# PingPong_388_2019_rev6.net
KiCad netlist of a schematic drawn in EAGLE
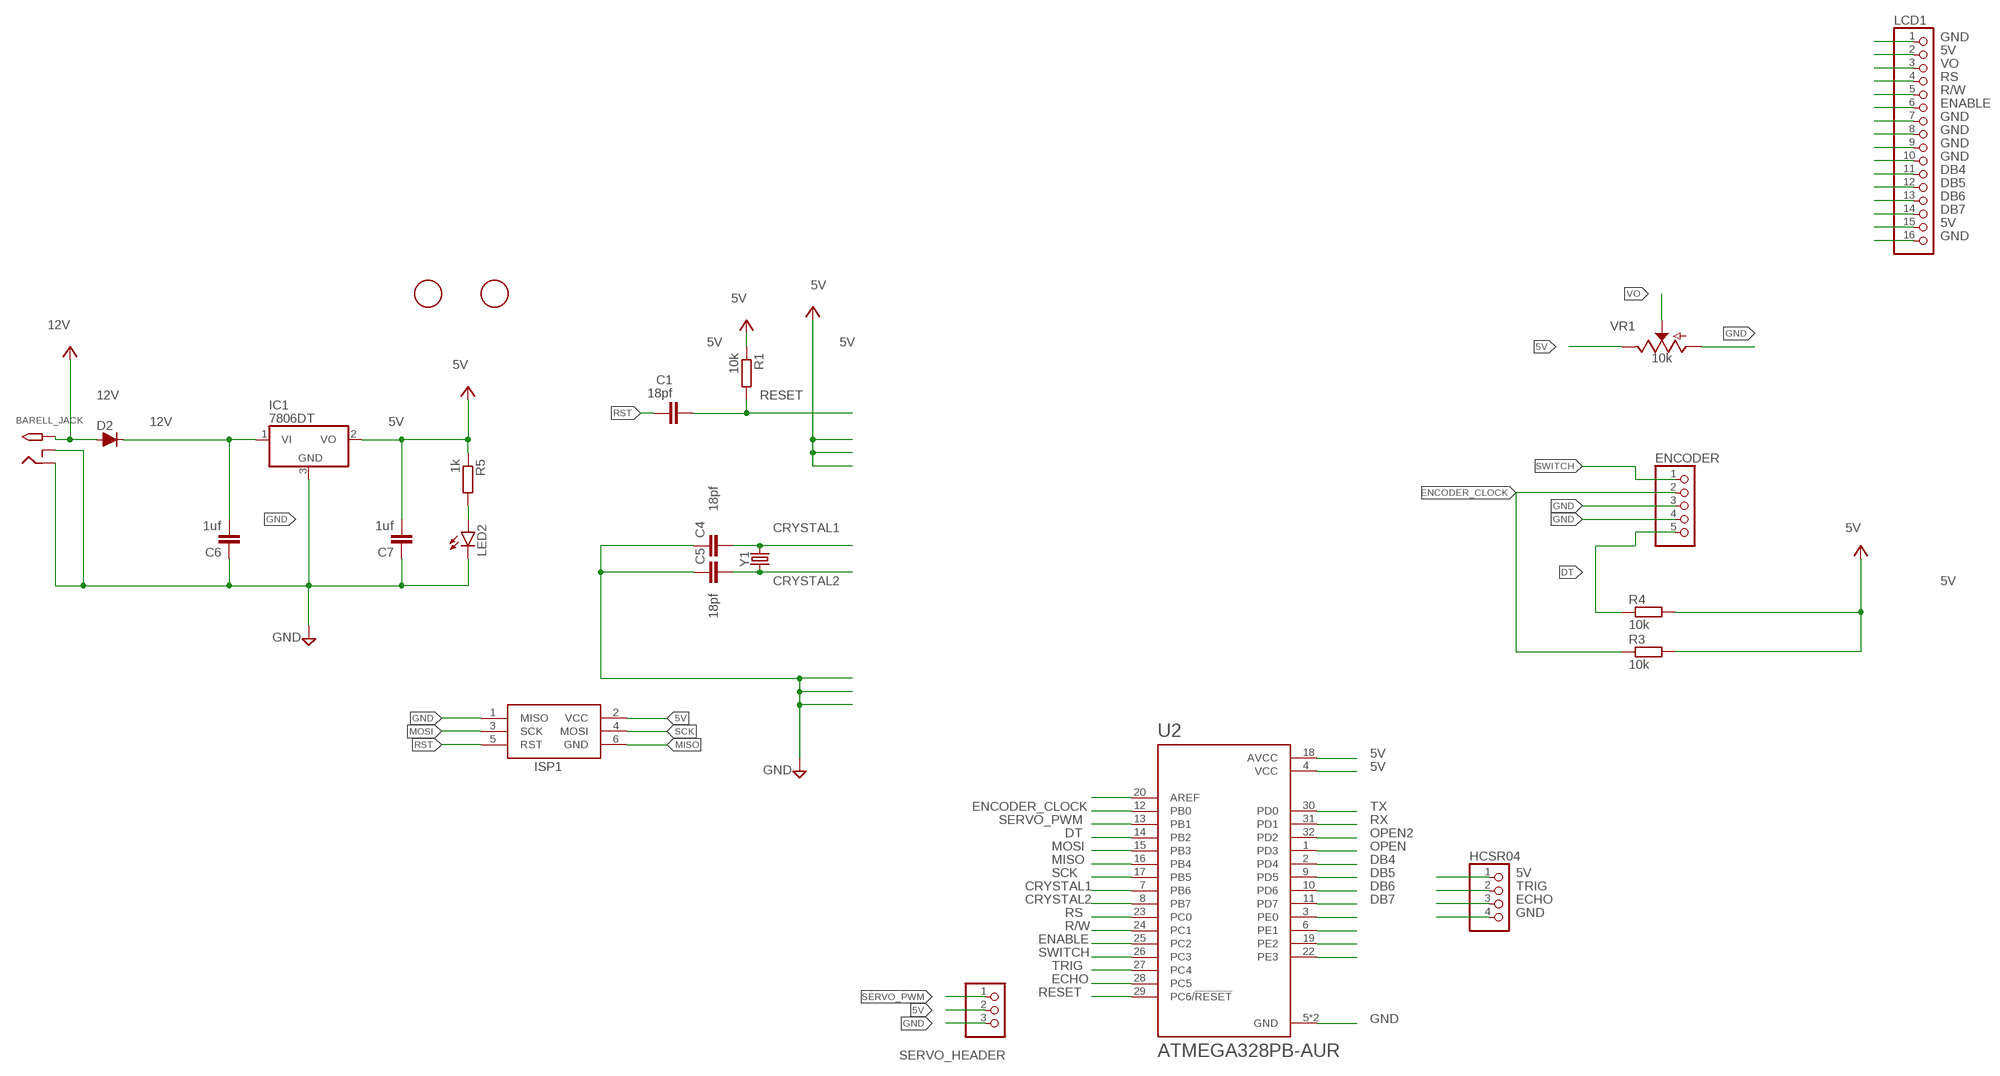
[diagram p0: schematic, sheet 1]

(export (version "E")
  (design (tool "Eeschema 10.0.6"))
  (components
    (comp (ref "BARELL_JACK")
      (value "2.1MMJACKTHM")
      (footprint "eagle-import:PJ-102A")
      (libsource (lib "eagle-import") (part "2.1MMJACKTHM"))
    )
    (comp (ref "C1")
      (value "18pf")
      (footprint "eagle-import:C0805")
      (libsource (lib "eagle-import") (part "C-EUC0805"))
    )
    (comp (ref "C4")
      (value "18pf")
      (footprint "eagle-import:C0805")
      (libsource (lib "eagle-import") (part "C-EUC0805"))
    )
    (comp (ref "C5")
      (value "18pf")
      (footprint "eagle-import:C0805")
      (libsource (lib "eagle-import") (part "C-EUC0805"))
    )
    (comp (ref "C6")
      (value "1uf")
      (footprint "eagle-import:C0805")
      (libsource (lib "eagle-import") (part "C-EUC0805"))
    )
    (comp (ref "C7")
      (value "1uf")
      (footprint "eagle-import:C0805")
      (libsource (lib "eagle-import") (part "C-EUC0805"))
    )
    (comp (ref "D2")
      (value "D-FILL-MLL-34")
      (footprint "eagle-import:MELF-MLL34")
      (libsource (lib "eagle-import") (part "D-FILL-MLL-34"))
    )
    (comp (ref "ENCODER")
      (value "PINHD-1X5")
      (footprint "eagle-import:1X05")
      (libsource (lib "eagle-import") (part "PINHD-1X5"))
    )
    (comp (ref "HCSR04")
      (value "PINHD-1X4")
      (footprint "eagle-import:1X04")
      (libsource (lib "eagle-import") (part "PINHD-1X4"))
    )
    (comp (ref "IC1")
      (value "7806DT")
      (footprint "eagle-import:TO252")
      (libsource (lib "eagle-import") (part "78DT06"))
    )
    (comp (ref "ISP1")
      (value "AVRISP-6")
      (footprint "eagle-import:AVRISP")
      (libsource (lib "eagle-import") (part "AVRISP-6"))
    )
    (comp (ref "LCD1")
      (value "PINHD-1X16")
      (footprint "eagle-import:1X16")
      (libsource (lib "eagle-import") (part "PINHD-1X16"))
    )
    (comp (ref "LED2")
      (value "LEDSML0805")
      (footprint "eagle-import:SML0805")
      (libsource (lib "eagle-import") (part "LEDSML0805"))
    )
    (comp (ref "R1")
      (value "10k")
      (footprint "eagle-import:R0805")
      (libsource (lib "eagle-import") (part "R-EU_R0805"))
    )
    (comp (ref "R3")
      (value "10k")
      (footprint "eagle-import:R0805")
      (libsource (lib "eagle-import") (part "R-EU_R0805"))
    )
    (comp (ref "R4")
      (value "10k")
      (footprint "eagle-import:R0805")
      (libsource (lib "eagle-import") (part "R-EU_R0805"))
    )
    (comp (ref "R5")
      (value "1k")
      (footprint "eagle-import:R0805")
      (libsource (lib "eagle-import") (part "R-EU_R0805"))
    )
    (comp (ref "SERVO_HEADER")
      (value "PINHD-1X3")
      (footprint "eagle-import:1X03")
      (libsource (lib "eagle-import") (part "PINHD-1X3"))
    )
    (comp (ref "U$3")
      (value "FIDUCIAL")
      (footprint "eagle-import:FIDUCIAL_1MM")
      (libsource (lib "eagle-import") (part "FIDUCIAL"))
    )
    (comp (ref "U$4")
      (value "FIDUCIAL")
      (footprint "eagle-import:FIDUCIAL_1MM")
      (libsource (lib "eagle-import") (part "FIDUCIAL"))
    )
    (comp (ref "U2")
      (value "ATMEGA328PB-AUR")
      (footprint "eagle-import:QFP80P900X900X120-32N")
      (fields (field (name "MF") "Microchip"))
      (libsource (lib "eagle-import") (part "ATMEGA328PB-AUR"))
    )
    (comp (ref "VR1")
      (value "10k")
      (footprint "eagle-import:POT-PTH-ALPS")
      (libsource (lib "eagle-import") (part "POTENTIOMETER-PTH-9MM-1/20W-20%"))
    )
    (comp (ref "Y1")
      (value "CRYSTALSMD-HC49UP")
      (footprint "eagle-import:HC49UP")
      (libsource (lib "eagle-import") (part "CRYSTALSMD-HC49UP"))
    )
  )
  (nets
    (net (code "1") (name "/CRYSTAL1") (class "Default")
      (node (ref "C4") (pin "2") (pinfunction "2_2") (pintype "passive"))
      (node (ref "U2") (pin "7") (pinfunction "PB6_7") (pintype "bidirectional"))
      (node (ref "Y1") (pin "2") (pinfunction "2_2") (pintype "passive"))
    )
    (net (code "2") (name "/CRYSTAL2") (class "Default")
      (node (ref "C5") (pin "2") (pinfunction "2_2") (pintype "passive"))
      (node (ref "U2") (pin "8") (pinfunction "PB7_8") (pintype "bidirectional"))
      (node (ref "Y1") (pin "1") (pinfunction "1_1") (pintype "passive"))
    )
    (net (code "3") (name "/DB4") (class "Default")
      (node (ref "LCD1") (pin "11") (pinfunction "11_11") (pintype "passive"))
      (node (ref "U2") (pin "2") (pinfunction "PD4_2") (pintype "bidirectional"))
    )
    (net (code "4") (name "/DB5") (class "Default")
      (node (ref "LCD1") (pin "12") (pinfunction "12_12") (pintype "passive"))
      (node (ref "U2") (pin "9") (pinfunction "PD5_9") (pintype "bidirectional"))
    )
    (net (code "5") (name "/DB6") (class "Default")
      (node (ref "LCD1") (pin "13") (pinfunction "13_13") (pintype "passive"))
      (node (ref "U2") (pin "10") (pinfunction "PD6_10") (pintype "bidirectional"))
    )
    (net (code "6") (name "/DB7") (class "Default")
      (node (ref "LCD1") (pin "14") (pinfunction "14_14") (pintype "passive"))
      (node (ref "U2") (pin "11") (pinfunction "PD7_11") (pintype "bidirectional"))
    )
    (net (code "7") (name "/ECHO") (class "Default")
      (node (ref "HCSR04") (pin "3") (pinfunction "3_3") (pintype "passive"))
      (node (ref "U2") (pin "28") (pinfunction "PC5_28") (pintype "bidirectional"))
    )
    (net (code "8") (name "/ENABLE") (class "Default")
      (node (ref "LCD1") (pin "6") (pinfunction "6_6") (pintype "passive"))
      (node (ref "U2") (pin "25") (pinfunction "PC2_25") (pintype "bidirectional"))
    )
    (net (code "9") (name "/OPEN") (class "Default")
      (node (ref "U2") (pin "1") (pinfunction "PD3_1") (pintype "bidirectional"))
    )
    (net (code "10") (name "/OPEN2") (class "Default")
      (node (ref "U2") (pin "32") (pinfunction "PD2_32") (pintype "bidirectional"))
    )
    (net (code "11") (name "/RESET") (class "Default")
      (node (ref "C1") (pin "2") (pinfunction "2_2") (pintype "passive"))
      (node (ref "R1") (pin "2") (pinfunction "2_2") (pintype "passive"))
      (node (ref "U2") (pin "29") (pinfunction "PC6/~{RESET}_29") (pintype "bidirectional"))
    )
    (net (code "12") (name "/RS") (class "Default")
      (node (ref "LCD1") (pin "4") (pinfunction "4_4") (pintype "passive"))
      (node (ref "U2") (pin "23") (pinfunction "PC0_23") (pintype "bidirectional"))
    )
    (net (code "13") (name "/RX") (class "Default")
      (node (ref "U2") (pin "31") (pinfunction "PD1_31") (pintype "bidirectional"))
    )
    (net (code "14") (name "/R{slash}W") (class "Default")
      (node (ref "LCD1") (pin "5") (pinfunction "5_5") (pintype "passive"))
      (node (ref "U2") (pin "24") (pinfunction "PC1_24") (pintype "bidirectional"))
    )
    (net (code "15") (name "/TRIG") (class "Default")
      (node (ref "HCSR04") (pin "2") (pinfunction "2_2") (pintype "passive"))
      (node (ref "U2") (pin "27") (pinfunction "PC4_27") (pintype "bidirectional"))
    )
    (net (code "16") (name "/TX") (class "Default")
      (node (ref "U2") (pin "30") (pinfunction "PD0_30") (pintype "bidirectional"))
    )
    (net (code "17") (name "5V") (class "Default")
      (node (ref "C7") (pin "2") (pinfunction "2_2") (pintype "passive"))
      (node (ref "HCSR04") (pin "1") (pinfunction "1_1") (pintype "passive"))
      (node (ref "IC1") (pin "2") (pinfunction "VO_2") (pintype "passive"))
      (node (ref "ISP1") (pin "2") (pinfunction "VCC_2") (pintype "power_in"))
      (node (ref "LCD1") (pin "15") (pinfunction "15_15") (pintype "passive"))
      (node (ref "LCD1") (pin "2") (pinfunction "2_2") (pintype "passive"))
      (node (ref "R1") (pin "1") (pinfunction "1_1") (pintype "passive"))
      (node (ref "R3") (pin "2") (pinfunction "2_2") (pintype "passive"))
      (node (ref "R4") (pin "2") (pinfunction "2_2") (pintype "passive"))
      (node (ref "R5") (pin "1") (pinfunction "1_1") (pintype "passive"))
      (node (ref "SERVO_HEADER") (pin "2") (pinfunction "2_2") (pintype "passive"))
      (node (ref "U2") (pin "18") (pinfunction "AVCC_18") (pintype "power_in"))
      (node (ref "U2") (pin "4") (pinfunction "VCC_4") (pintype "power_in"))
      (node (ref "VR1") (pin "P$1") (pinfunction "E_P$1") (pintype "passive"))
    )
    (net (code "18") (name "12V") (class "Default")
      (node (ref "BARELL_JACK") (pin "TIP") (pinfunction "TIP_TIP") (pintype "bidirectional"))
      (node (ref "C6") (pin "2") (pinfunction "2_2") (pintype "passive"))
      (node (ref "D2") (pin "1") (pinfunction "C_1") (pintype "passive"))
      (node (ref "D2") (pin "2") (pinfunction "A_2") (pintype "passive"))
      (node (ref "IC1") (pin "1") (pinfunction "VI_1") (pintype "input"))
    )
    (net (code "19") (name "DT") (class "Default")
      (node (ref "ENCODER") (pin "5") (pinfunction "5_5") (pintype "passive"))
      (node (ref "R4") (pin "1") (pinfunction "1_1") (pintype "passive"))
      (node (ref "U2") (pin "14") (pinfunction "PB2_14") (pintype "bidirectional"))
    )
    (net (code "20") (name "ENCODER_CLOCK") (class "Default")
      (node (ref "ENCODER") (pin "2") (pinfunction "2_2") (pintype "passive"))
      (node (ref "R3") (pin "1") (pinfunction "1_1") (pintype "passive"))
      (node (ref "U2") (pin "12") (pinfunction "PB0_12") (pintype "bidirectional"))
    )
    (net (code "21") (name "GND") (class "Default")
      (node (ref "BARELL_JACK") (pin "RING") (pinfunction "RING_RING") (pintype "bidirectional"))
      (node (ref "BARELL_JACK") (pin "RING_SW") (pinfunction "RING_SW_RING_SW") (pintype "bidirectional"))
      (node (ref "C4") (pin "1") (pinfunction "1_1") (pintype "passive"))
      (node (ref "C5") (pin "1") (pinfunction "1_1") (pintype "passive"))
      (node (ref "C6") (pin "1") (pinfunction "1_1") (pintype "passive"))
      (node (ref "C7") (pin "1") (pinfunction "1_1") (pintype "passive"))
      (node (ref "ENCODER") (pin "3") (pinfunction "3_3") (pintype "passive"))
      (node (ref "ENCODER") (pin "4") (pinfunction "4_4") (pintype "passive"))
      (node (ref "HCSR04") (pin "4") (pinfunction "4_4") (pintype "passive"))
      (node (ref "IC1") (pin "3") (pinfunction "GND_3") (pintype "passive"))
      (node (ref "ISP1") (pin "1") (pinfunction "MISO_1") (pintype "input"))
      (node (ref "LCD1") (pin "1") (pinfunction "1_1") (pintype "passive"))
      (node (ref "LCD1") (pin "10") (pinfunction "10_10") (pintype "passive"))
      (node (ref "LCD1") (pin "16") (pinfunction "16_16") (pintype "passive"))
      (node (ref "LCD1") (pin "7") (pinfunction "7_7") (pintype "passive"))
      (node (ref "LCD1") (pin "8") (pinfunction "8_8") (pintype "passive"))
      (node (ref "LCD1") (pin "9") (pinfunction "9_9") (pintype "passive"))
      (node (ref "LED2") (pin "C") (pinfunction "C_C") (pintype "passive"))
      (node (ref "SERVO_HEADER") (pin "3") (pinfunction "3_3") (pintype "passive"))
      (node (ref "U2") (pin "21") (pinfunction "GND_21") (pintype "power_in"))
      (node (ref "U2") (pin "5") (pinfunction "GND_5") (pintype "power_in"))
      (node (ref "VR1") (pin "P$3") (pinfunction "A_P$3") (pintype "passive"))
    )
    (net (code "22") (name "MISO") (class "Default")
      (node (ref "ISP1") (pin "6") (pinfunction "GND_6") (pintype "power_in"))
      (node (ref "U2") (pin "16") (pinfunction "PB4_16") (pintype "bidirectional"))
    )
    (net (code "23") (name "MOSI") (class "Default")
      (node (ref "ISP1") (pin "3") (pinfunction "SCK_3") (pintype "output"))
      (node (ref "U2") (pin "15") (pinfunction "PB3_15") (pintype "bidirectional"))
    )
    (net (code "24") (name "Net-(LED2-PadA)") (class "Default")
      (node (ref "LED2") (pin "A") (pinfunction "A_A") (pintype "passive"))
      (node (ref "R5") (pin "2") (pinfunction "2_2") (pintype "passive"))
    )
    (net (code "25") (name "RST") (class "Default")
      (node (ref "C1") (pin "1") (pinfunction "1_1") (pintype "passive"))
      (node (ref "ISP1") (pin "5") (pinfunction "RST_5") (pintype "output"))
    )
    (net (code "26") (name "SCK") (class "Default")
      (node (ref "ISP1") (pin "4") (pinfunction "MOSI_4") (pintype "output"))
      (node (ref "U2") (pin "17") (pinfunction "PB5_17") (pintype "bidirectional"))
    )
    (net (code "27") (name "SERVO_PWM") (class "Default")
      (node (ref "SERVO_HEADER") (pin "1") (pinfunction "1_1") (pintype "passive"))
      (node (ref "U2") (pin "13") (pinfunction "PB1_13") (pintype "bidirectional"))
    )
    (net (code "28") (name "SWITCH") (class "Default")
      (node (ref "ENCODER") (pin "1") (pinfunction "1_1") (pintype "passive"))
      (node (ref "U2") (pin "26") (pinfunction "PC3_26") (pintype "bidirectional"))
    )
    (net (code "29") (name "VO") (class "Default")
      (node (ref "LCD1") (pin "3") (pinfunction "3_3") (pintype "passive"))
      (node (ref "VR1") (pin "P$2") (pinfunction "S_P$2") (pintype "passive"))
    )
    (net (code "30") (name "unconnected-(U2-AREF-Pad20)") (class "Default")
      (node (ref "U2") (pin "20") (pinfunction "AREF_20") (pintype "input"))
    )
    (net (code "31") (name "unconnected-(U2-PE0-Pad3)") (class "Default")
      (node (ref "U2") (pin "3") (pinfunction "PE0_3") (pintype "bidirectional"))
    )
    (net (code "32") (name "unconnected-(U2-PE1-Pad6)") (class "Default")
      (node (ref "U2") (pin "6") (pinfunction "PE1_6") (pintype "bidirectional"))
    )
    (net (code "33") (name "unconnected-(U2-PE2-Pad19)") (class "Default")
      (node (ref "U2") (pin "19") (pinfunction "PE2_19") (pintype "bidirectional"))
    )
    (net (code "34") (name "unconnected-(U2-PE3-Pad22)") (class "Default")
      (node (ref "U2") (pin "22") (pinfunction "PE3_22") (pintype "bidirectional"))
    )
  )
)
